# W5500.net
KiCad netlist of a schematic drawn in Altium Designer
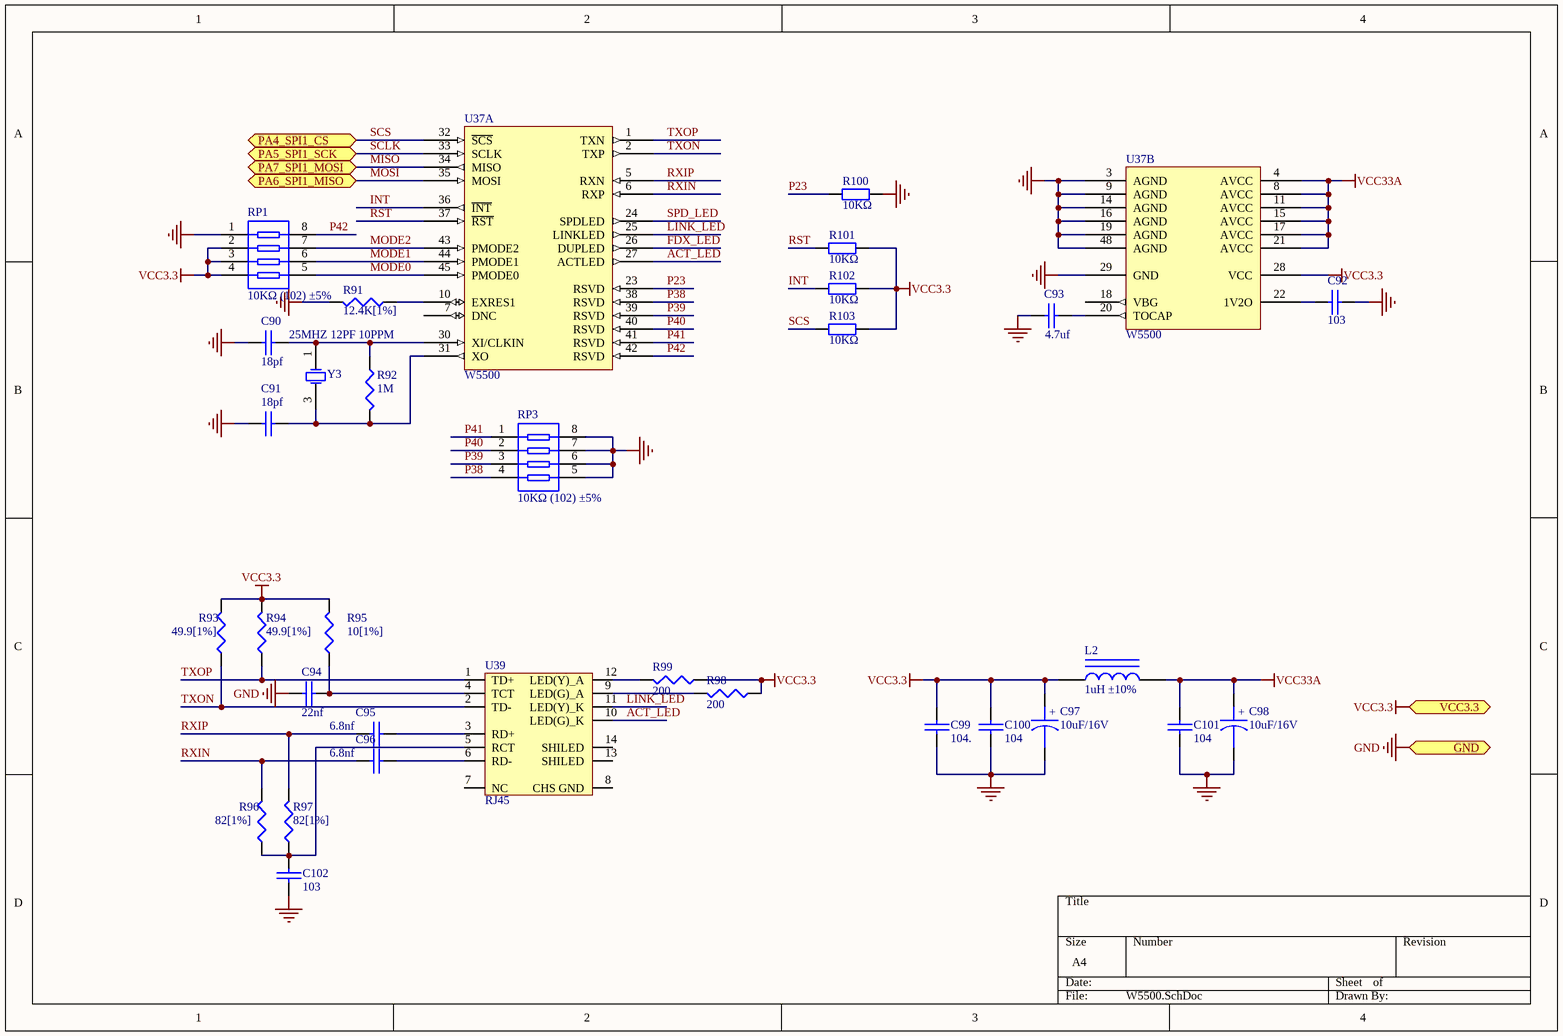
[diagram p0: W5500.SchDoc]

(export (version "E")
  (design (tool "Eeschema 10.0.6"))
  (components
    (comp (ref "C90")
      (value "18pf")
      (footprint "0603_C")
      (description "Capacitor")
      (libsource (lib "*") (part "CAP"))
    )
    (comp (ref "C91")
      (value "18pf")
      (footprint "0603_C")
      (description "Capacitor")
      (libsource (lib "*") (part "CAP"))
    )
    (comp (ref "C92")
      (value "103")
      (footprint "0603_C")
      (description "Capacitor")
      (libsource (lib "*") (part "CAP"))
    )
    (comp (ref "C93")
      (value "4.7uf")
      (footprint "0603_C")
      (description "Capacitor")
      (libsource (lib "*") (part "CAP"))
    )
    (comp (ref "C94")
      (value "22nf")
      (footprint "0603_C")
      (description "Capacitor")
      (libsource (lib "*") (part "CAP"))
    )
    (comp (ref "C95")
      (value "6.8nf")
      (footprint "0603_C")
      (description "Capacitor")
      (libsource (lib "*") (part "CAP"))
    )
    (comp (ref "C96")
      (value "6.8nf")
      (footprint "0603_C")
      (description "Capacitor")
      (libsource (lib "*") (part "CAP"))
    )
    (comp (ref "C97")
      (value "10uF/16V")
      (footprint "3216")
      (description "Capacitor")
      (libsource (lib "*") (part "CAPACITOR POL"))
    )
    (comp (ref "C98")
      (value "10uF/16V")
      (footprint "3216")
      (description "Capacitor")
      (libsource (lib "*") (part "CAPACITOR POL"))
    )
    (comp (ref "C99")
      (value "104.")
      (footprint "0603_C")
      (description "Capacitor")
      (libsource (lib "*") (part "CAP"))
    )
    (comp (ref "C100")
      (value "104")
      (footprint "0603_C")
      (description "Capacitor")
      (libsource (lib "*") (part "CAP"))
    )
    (comp (ref "C101")
      (value "104")
      (footprint "0603_C")
      (description "Capacitor")
      (libsource (lib "*") (part "CAP"))
    )
    (comp (ref "C102")
      (value "103")
      (footprint "0603_C")
      (description "Capacitor")
      (libsource (lib "*") (part "CAP"))
    )
    (comp (ref "L2")
      (value "1uH ±10%")
      (footprint "0805_L")
      (description "贴片电感")
      (libsource (lib "Miscellaneous Devices LC") (part "0805 1uH 10%"))
    )
    (comp (ref "R91") (value "12.4K[1%]") (footprint "0603_R") (libsource (lib "*") (part "RES1")))
    (comp (ref "R92") (value "1M") (footprint "0603_R") (libsource (lib "*") (part "RES1")))
    (comp (ref "R93") (value "49.9[1%]") (footprint "0603_R") (libsource (lib "*") (part "RES1")))
    (comp (ref "R94") (value "49.9[1%]") (footprint "0603_R") (libsource (lib "*") (part "RES1")))
    (comp (ref "R95") (value "10[1%]") (footprint "0603_R") (libsource (lib "*") (part "RES1")))
    (comp (ref "R96") (value "82[1%]") (footprint "0603_R") (libsource (lib "*") (part "RES1")))
    (comp (ref "R97") (value "82[1%]") (footprint "0603_R") (libsource (lib "*") (part "RES1")))
    (comp (ref "R98") (value "200") (footprint "0603_R") (libsource (lib "*") (part "RES1")))
    (comp (ref "R99") (value "200") (footprint "0603_R") (libsource (lib "*") (part "RES1")))
    (comp (ref "R100")
      (value "10KΩ")
      (footprint "0603_R")
      (description "贴片电阻")
      (libsource (lib "Miscellaneous Devices LC") (part "0603 1.1KΩ (1101) 1%"))
    )
    (comp (ref "R101")
      (value "10KΩ")
      (footprint "0603_R")
      (description "贴片电阻")
      (libsource (lib "Miscellaneous Devices LC") (part "0603 1.1KΩ (1101) 1%"))
    )
    (comp (ref "R102")
      (value "10KΩ")
      (footprint "0603_R")
      (description "贴片电阻")
      (libsource (lib "Miscellaneous Devices LC") (part "0603 1.1KΩ (1101) 1%"))
    )
    (comp (ref "R103")
      (value "10KΩ")
      (footprint "0603_R")
      (description "贴片电阻")
      (libsource (lib "Miscellaneous Devices LC") (part "0603 1.1KΩ (1101) 1%"))
    )
    (comp (ref "RP1")
      (value "10KΩ (102) ±5%")
      (footprint "0603_Rx4")
      (description "贴片排阻")
      (libsource (lib "Miscellaneous Devices LC") (part "0603*4  1KΩ (102) 5%"))
    )
    (comp (ref "RP3")
      (value "10KΩ (102) ±5%")
      (footprint "0603_Rx4")
      (description "贴片排阻")
      (libsource (lib "Miscellaneous Devices LC") (part "0603*4  1KΩ (102) 5%"))
    )
    (comp (ref "U37") (value "W5500") (footprint "LQFP-48_7x7x05P") (libsource (lib "*") (part "W5500")))
    (comp (ref "U39") (value "RJ45") (footprint "HR911105A") (libsource (lib "EXPLORER") (part "HR911105")))
    (comp (ref "Y3")
      (value "25MHZ 12PF 10PPM")
      (footprint "SMD-3225_4P")
      (description "贴片晶振")
      (libsource (lib "Miscellaneous Devices LC") (part "SMD-3225_4P  25MHZ 12PF 10PPM"))
    )
  )
  (nets
    (net (code "1") (name "/ACT_LED") (class "Default")
      (node (ref "U37") (pin "27") (pinfunction "ACTLED_27") (pintype "output"))
      (node (ref "U39") (pin "10") (pinfunction "LED(G)_K_10") (pintype "passive"))
    )
    (net (code "2") (name "/FDX_LED") (class "Default")
      (node (ref "U37") (pin "26") (pinfunction "DUPLED_26") (pintype "output"))
    )
    (net (code "3") (name "/INT") (class "Default")
      (node (ref "R102") (pin "1") (pinfunction "1_1") (pintype "passive"))
      (node (ref "U37") (pin "36") (pinfunction "~{INT}_36") (pintype "output"))
    )
    (net (code "4") (name "/LINK_LED") (class "Default")
      (node (ref "U37") (pin "25") (pinfunction "LINKLED_25") (pintype "output"))
      (node (ref "U39") (pin "11") (pinfunction "LED(Y)_K_11") (pintype "passive"))
    )
    (net (code "5") (name "/MISO") (class "Default")
      (node (ref "U37") (pin "34") (pinfunction "MISO_34") (pintype "output"))
    )
    (net (code "6") (name "/MODE0") (class "Default")
      (node (ref "RP1") (pin "5") (pinfunction "5_5") (pintype "passive"))
      (node (ref "U37") (pin "45") (pinfunction "PMODE0_45") (pintype "input"))
    )
    (net (code "7") (name "/MODE1") (class "Default")
      (node (ref "RP1") (pin "6") (pinfunction "6_6") (pintype "passive"))
      (node (ref "U37") (pin "44") (pinfunction "PMODE1_44") (pintype "input"))
    )
    (net (code "8") (name "/MODE2") (class "Default")
      (node (ref "RP1") (pin "7") (pinfunction "7_7") (pintype "passive"))
      (node (ref "U37") (pin "43") (pinfunction "PMODE2_43") (pintype "input"))
    )
    (net (code "9") (name "/MOSI") (class "Default")
      (node (ref "U37") (pin "35") (pinfunction "MOSI_35") (pintype "input"))
    )
    (net (code "10") (name "/P23") (class "Default")
      (node (ref "R100") (pin "1") (pinfunction "1_1") (pintype "passive"))
      (node (ref "U37") (pin "23") (pinfunction "RSVD_23") (pintype "input"))
    )
    (net (code "11") (name "/P38") (class "Default")
      (node (ref "RP3") (pin "4") (pinfunction "4_4") (pintype "passive"))
      (node (ref "U37") (pin "38") (pinfunction "RSVD_38") (pintype "input"))
    )
    (net (code "12") (name "/P39") (class "Default")
      (node (ref "RP3") (pin "3") (pinfunction "3_3") (pintype "passive"))
      (node (ref "U37") (pin "39") (pinfunction "RSVD_39") (pintype "input"))
    )
    (net (code "13") (name "/P40") (class "Default")
      (node (ref "RP3") (pin "2") (pinfunction "2_2") (pintype "passive"))
      (node (ref "U37") (pin "40") (pinfunction "RSVD_40") (pintype "input"))
    )
    (net (code "14") (name "/P41") (class "Default")
      (node (ref "RP3") (pin "1") (pinfunction "1_1") (pintype "passive"))
      (node (ref "U37") (pin "41") (pinfunction "RSVD_41") (pintype "input"))
    )
    (net (code "15") (name "/P42") (class "Default")
      (node (ref "RP1") (pin "8") (pinfunction "8_8") (pintype "passive"))
      (node (ref "U37") (pin "42") (pinfunction "RSVD_42") (pintype "input"))
    )
    (net (code "16") (name "/RST") (class "Default")
      (node (ref "R101") (pin "1") (pinfunction "1_1") (pintype "passive"))
      (node (ref "U37") (pin "37") (pinfunction "~{RST}_37") (pintype "input"))
    )
    (net (code "17") (name "/RXIN") (class "Default")
      (node (ref "C96") (pin "1") (pinfunction "1_1") (pintype "passive"))
      (node (ref "R96") (pin "2") (pinfunction "2_2") (pintype "passive"))
      (node (ref "U37") (pin "6") (pinfunction "RXP_6") (pintype "input"))
    )
    (net (code "18") (name "/RXIP") (class "Default")
      (node (ref "C95") (pin "1") (pinfunction "1_1") (pintype "passive"))
      (node (ref "R97") (pin "2") (pinfunction "2_2") (pintype "passive"))
      (node (ref "U37") (pin "5") (pinfunction "RXN_5") (pintype "input"))
    )
    (net (code "19") (name "/SCLK") (class "Default")
      (node (ref "U37") (pin "33") (pinfunction "SCLK_33") (pintype "input"))
    )
    (net (code "20") (name "/SCS") (class "Default")
      (node (ref "R103") (pin "1") (pinfunction "1_1") (pintype "passive"))
      (node (ref "U37") (pin "32") (pinfunction "~{SCS}_32") (pintype "input"))
    )
    (net (code "21") (name "/SPD_LED") (class "Default")
      (node (ref "U37") (pin "24") (pinfunction "SPDLED_24") (pintype "output"))
    )
    (net (code "22") (name "/TXON") (class "Default")
      (node (ref "R93") (pin "1") (pinfunction "1_1") (pintype "passive"))
      (node (ref "U37") (pin "2") (pinfunction "TXP_2") (pintype "output"))
      (node (ref "U39") (pin "2") (pinfunction "TD-_2") (pintype "passive"))
    )
    (net (code "23") (name "/TXOP") (class "Default")
      (node (ref "R94") (pin "1") (pinfunction "1_1") (pintype "passive"))
      (node (ref "U37") (pin "1") (pinfunction "TXN_1") (pintype "output"))
      (node (ref "U39") (pin "1") (pinfunction "TD+_1") (pintype "passive"))
    )
    (net (code "24") (name "GND") (class "Default")
      (node (ref "C100") (pin "2") (pinfunction "2_2") (pintype "passive"))
      (node (ref "C101") (pin "2") (pinfunction "2_2") (pintype "passive"))
      (node (ref "C102") (pin "2") (pinfunction "2_2") (pintype "passive"))
      (node (ref "C90") (pin "2") (pinfunction "2_2") (pintype "passive"))
      (node (ref "C91") (pin "2") (pinfunction "2_2") (pintype "passive"))
      (node (ref "C92") (pin "1") (pinfunction "1_1") (pintype "passive"))
      (node (ref "C93") (pin "2") (pinfunction "2_2") (pintype "passive"))
      (node (ref "C94") (pin "1") (pinfunction "1_1") (pintype "passive"))
      (node (ref "C97") (pin "2") (pinfunction "2_2") (pintype "passive"))
      (node (ref "C98") (pin "2") (pinfunction "2_2") (pintype "passive"))
      (node (ref "C99") (pin "2") (pinfunction "2_2") (pintype "passive"))
      (node (ref "R100") (pin "2") (pinfunction "2_2") (pintype "passive"))
      (node (ref "R91") (pin "2") (pinfunction "2_2") (pintype "passive"))
      (node (ref "RP1") (pin "1") (pinfunction "1_1") (pintype "passive"))
      (node (ref "RP3") (pin "5") (pinfunction "5_5") (pintype "passive"))
      (node (ref "RP3") (pin "6") (pinfunction "6_6") (pintype "passive"))
      (node (ref "RP3") (pin "7") (pinfunction "7_7") (pintype "passive"))
      (node (ref "RP3") (pin "8") (pinfunction "8_8") (pintype "passive"))
      (node (ref "U37") (pin "14") (pinfunction "AGND_14") (pintype "power_in"))
      (node (ref "U37") (pin "16") (pinfunction "AGND_16") (pintype "power_in"))
      (node (ref "U37") (pin "19") (pinfunction "AGND_19") (pintype "power_in"))
      (node (ref "U37") (pin "29") (pinfunction "GND_29") (pintype "power_in"))
      (node (ref "U37") (pin "3") (pinfunction "AGND_3") (pintype "power_in"))
      (node (ref "U37") (pin "48") (pinfunction "AGND_48") (pintype "power_in"))
      (node (ref "U37") (pin "9") (pinfunction "AGND_9") (pintype "power_in"))
    )
    (net (code "25") (name "Net-(U37A-EXRES1)") (class "Default")
      (node (ref "R91") (pin "1") (pinfunction "1_1") (pintype "passive"))
      (node (ref "U37") (pin "10") (pinfunction "EXRES1_10") (pintype "bidirectional"))
    )
    (net (code "26") (name "Net-(U37A-XI{slash}CLKIN)") (class "Default")
      (node (ref "C90") (pin "1") (pinfunction "1_1") (pintype "passive"))
      (node (ref "R92") (pin "1") (pinfunction "1_1") (pintype "passive"))
      (node (ref "U37") (pin "30") (pinfunction "XI/CLKIN_30") (pintype "input"))
      (node (ref "Y3") (pin "1") (pinfunction "OSC1_1") (pintype "passive"))
    )
    (net (code "27") (name "Net-(U37A-XO)") (class "Default")
      (node (ref "C91") (pin "1") (pinfunction "1_1") (pintype "passive"))
      (node (ref "R92") (pin "2") (pinfunction "2_2") (pintype "passive"))
      (node (ref "U37") (pin "31") (pinfunction "XO_31") (pintype "output"))
      (node (ref "Y3") (pin "3") (pinfunction "OSC2_3") (pintype "passive"))
    )
    (net (code "28") (name "Net-(U37B-1V2O)") (class "Default")
      (node (ref "C92") (pin "2") (pinfunction "2_2") (pintype "passive"))
      (node (ref "U37") (pin "22") (pinfunction "1V2O_22") (pintype "power_in"))
    )
    (net (code "29") (name "Net-(U37B-TOCAP)") (class "Default")
      (node (ref "C93") (pin "1") (pinfunction "1_1") (pintype "passive"))
      (node (ref "U37") (pin "20") (pinfunction "TOCAP_20") (pintype "output"))
    )
    (net (code "30") (name "Net-(U39-LED(G)_A)") (class "Default")
      (node (ref "R98") (pin "2") (pinfunction "2_2") (pintype "passive"))
      (node (ref "U39") (pin "9") (pinfunction "LED(G)_A_9") (pintype "passive"))
    )
    (net (code "31") (name "Net-(U39-LED(Y)_A)") (class "Default")
      (node (ref "R99") (pin "2") (pinfunction "2_2") (pintype "passive"))
      (node (ref "U39") (pin "12") (pinfunction "LED(Y)_A_12") (pintype "passive"))
    )
    (net (code "32") (name "Net-(U39-RCT)") (class "Default")
      (node (ref "C102") (pin "1") (pinfunction "1_1") (pintype "passive"))
      (node (ref "R96") (pin "1") (pinfunction "1_1") (pintype "passive"))
      (node (ref "R97") (pin "1") (pinfunction "1_1") (pintype "passive"))
      (node (ref "U39") (pin "5") (pinfunction "RCT_5") (pintype "passive"))
    )
    (net (code "33") (name "Net-(U39-RD+)") (class "Default")
      (node (ref "C95") (pin "2") (pinfunction "2_2") (pintype "passive"))
      (node (ref "U39") (pin "3") (pinfunction "RD+_3") (pintype "passive"))
    )
    (net (code "34") (name "Net-(U39-RD-)") (class "Default")
      (node (ref "C96") (pin "2") (pinfunction "2_2") (pintype "passive"))
      (node (ref "U39") (pin "6") (pinfunction "RD-_6") (pintype "passive"))
    )
    (net (code "35") (name "Net-(U39-TCT)") (class "Default")
      (node (ref "C94") (pin "2") (pinfunction "2_2") (pintype "passive"))
      (node (ref "R95") (pin "1") (pinfunction "1_1") (pintype "passive"))
      (node (ref "U39") (pin "4") (pinfunction "TCT_4") (pintype "passive"))
    )
    (net (code "36") (name "VCC3.3") (class "Default")
      (node (ref "C100") (pin "1") (pinfunction "1_1") (pintype "passive"))
      (node (ref "C97") (pin "1") (pinfunction "1_1") (pintype "passive"))
      (node (ref "C99") (pin "1") (pinfunction "1_1") (pintype "passive"))
      (node (ref "L2") (pin "1") (pinfunction "1_1") (pintype "passive"))
      (node (ref "R101") (pin "2") (pinfunction "2_2") (pintype "passive"))
      (node (ref "R102") (pin "2") (pinfunction "2_2") (pintype "passive"))
      (node (ref "R103") (pin "2") (pinfunction "2_2") (pintype "passive"))
      (node (ref "R93") (pin "2") (pinfunction "2_2") (pintype "passive"))
      (node (ref "R94") (pin "2") (pinfunction "2_2") (pintype "passive"))
      (node (ref "R95") (pin "2") (pinfunction "2_2") (pintype "passive"))
      (node (ref "R98") (pin "1") (pinfunction "1_1") (pintype "passive"))
      (node (ref "R99") (pin "1") (pinfunction "1_1") (pintype "passive"))
      (node (ref "RP1") (pin "2") (pinfunction "2_2") (pintype "passive"))
      (node (ref "RP1") (pin "3") (pinfunction "3_3") (pintype "passive"))
      (node (ref "RP1") (pin "4") (pinfunction "4_4") (pintype "passive"))
      (node (ref "U37") (pin "28") (pinfunction "VCC_28") (pintype "power_in"))
    )
    (net (code "37") (name "VCC33A") (class "Default")
      (node (ref "C101") (pin "1") (pinfunction "1_1") (pintype "passive"))
      (node (ref "C98") (pin "1") (pinfunction "1_1") (pintype "passive"))
      (node (ref "L2") (pin "2") (pinfunction "2_2") (pintype "passive"))
      (node (ref "U37") (pin "11") (pinfunction "AVCC_11") (pintype "power_in"))
      (node (ref "U37") (pin "15") (pinfunction "AVCC_15") (pintype "power_in"))
      (node (ref "U37") (pin "17") (pinfunction "AVCC_17") (pintype "power_in"))
      (node (ref "U37") (pin "21") (pinfunction "AVCC_21") (pintype "power_in"))
      (node (ref "U37") (pin "4") (pinfunction "AVCC_4") (pintype "power_in"))
      (node (ref "U37") (pin "8") (pinfunction "AVCC_8") (pintype "power_in"))
    )
    (net (code "38") (name "unconnected-(U37A-DNC-Pad7)") (class "Default")
      (node (ref "U37") (pin "7") (pinfunction "DNC_7") (pintype "bidirectional"))
    )
    (net (code "39") (name "unconnected-(U37B-VBG-Pad18)") (class "Default")
      (node (ref "U37") (pin "18") (pinfunction "VBG_18") (pintype "output"))
    )
    (net (code "40") (name "unconnected-(U39-CHS_GND-Pad8)") (class "Default")
      (node (ref "U39") (pin "8") (pinfunction "CHS_GND_8") (pintype "passive"))
    )
    (net (code "41") (name "unconnected-(U39-NC-Pad7)") (class "Default")
      (node (ref "U39") (pin "7") (pinfunction "NC_7") (pintype "passive"))
    )
    (net (code "42") (name "unconnected-(U39-SHILED-Pad13)") (class "Default")
      (node (ref "U39") (pin "13") (pinfunction "SHILED_13") (pintype "passive"))
    )
    (net (code "43") (name "unconnected-(U39-SHILED-Pad14)") (class "Default")
      (node (ref "U39") (pin "14") (pinfunction "SHILED_14") (pintype "passive"))
    )
  )
)
